# 09_-_PERIPHERALS_B.net
KiCad netlist of a schematic drawn in Altium Designer
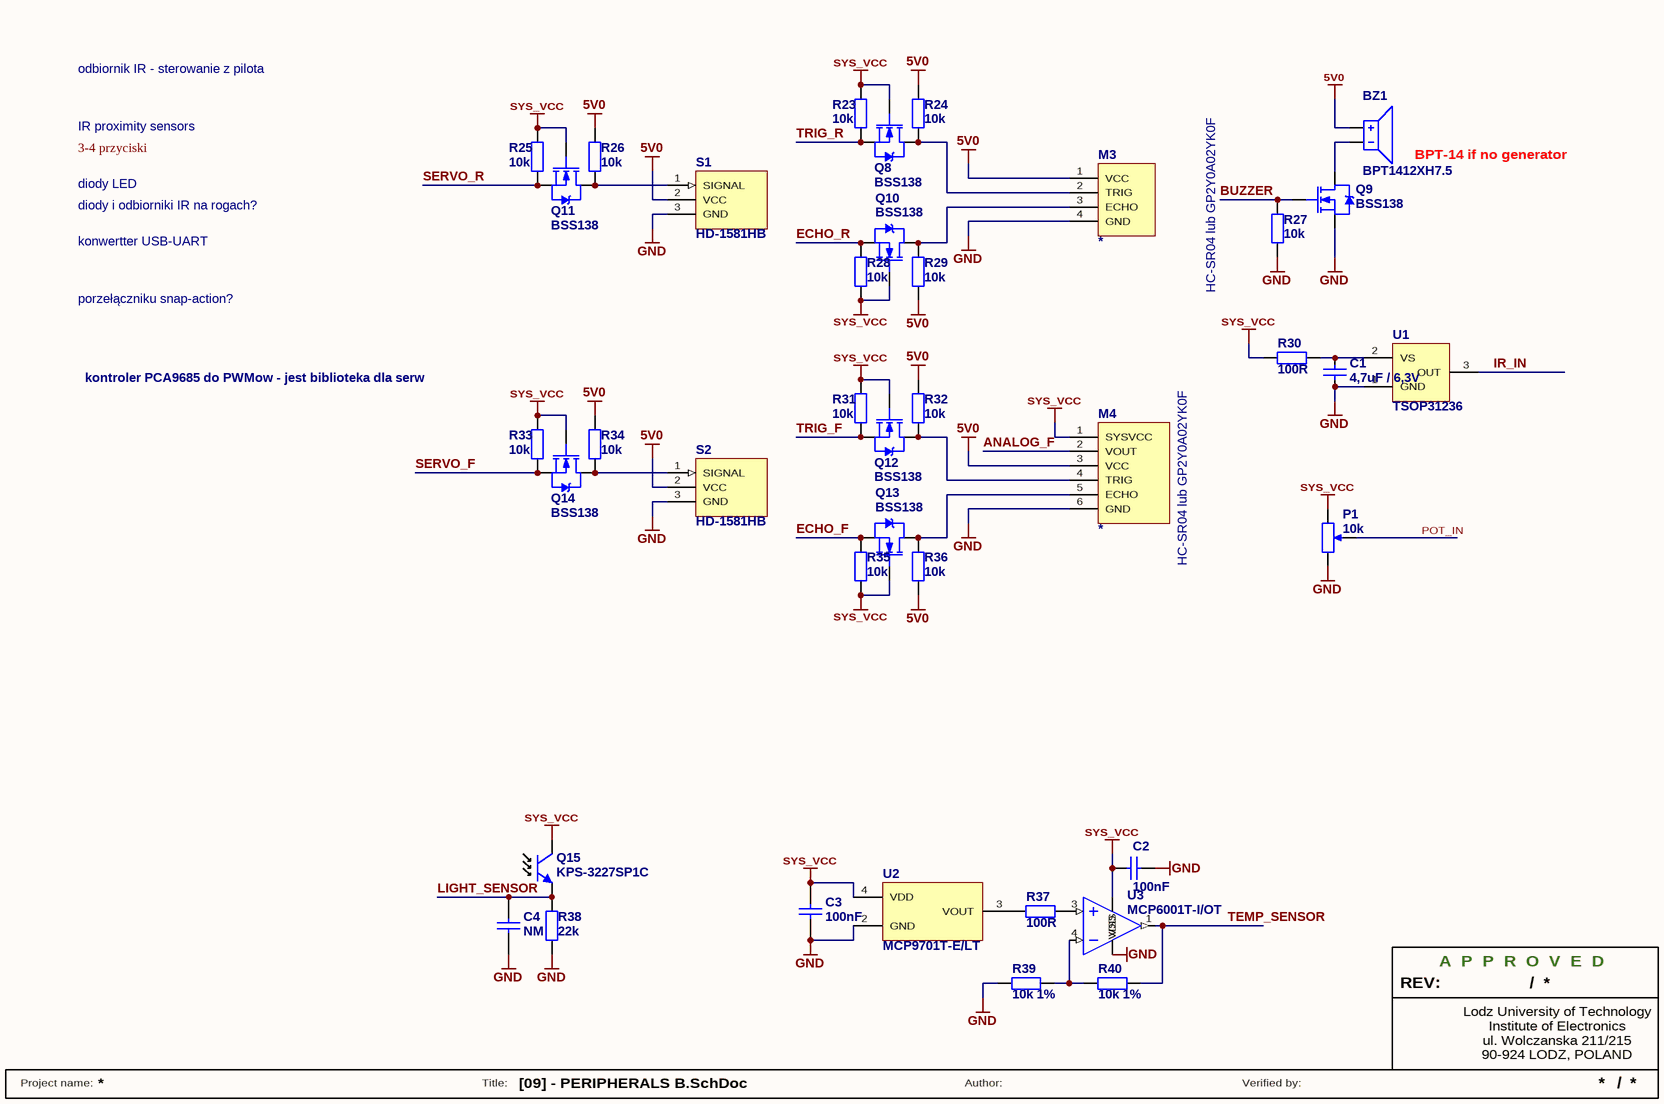
[diagram p0: [09] - PERIPHERALS B.SchDoc]

(export (version "E")
  (design (tool "Eeschema 10.0.6"))
  (components
    (comp (ref "BZ1")
      (value "BPT1412XH7.5")
      (footprint "BUZ-13,8-7,6")
      (description "Piezoelectric Sound Transducer: 5Vp-p; 4kHz; O:14mm; with generator")
      (fields (field (name "PUBLISHER") "Altium Limited"))
      (libsource (lib "sounders") (part "BPT1412XH7.5"))
    )
    (comp (ref "C1")
      (value "4,7uF / 6,3V")
      (footprint "C0805")
      (description "Capacitor")
      (libsource (lib "capacitors") (part "Cap"))
    )
    (comp (ref "C2")
      (value "100nF")
      (footprint "C0805")
      (description "Capacitor")
      (libsource (lib "") (part "Cap_1"))
    )
    (comp (ref "C3")
      (value "100nF")
      (footprint "C0805")
      (description "Capacitor")
      (libsource (lib "") (part "Cap_2"))
    )
    (comp (ref "C4")
      (value "NM")
      (footprint "C0805")
      (description "Capacitor")
      (libsource (lib "") (part "Cap_2"))
    )
    (comp (ref "M3") (value "*") (footprint "HC-SR04") (libsource (lib "other_modules") (part "HC-SR04")))
    (comp (ref "M4")
      (value "*")
      (footprint "HC-SR04_UNIV")
      (libsource (lib "other_modules") (part "HC-SR04_UNIVERSAL"))
    )
    (comp (ref "P1")
      (value "10k")
      (footprint "RK09K113004U")
      (description "RK09K113004U")
      (libsource (lib "resistors") (part "RK09K113004U"))
    )
    (comp (ref "Q8")
      (value "BSS138")
      (footprint "SOT-23")
      (description "N-Channel Enhancement Mode Vertical DMOS FET")
      (fields (field (name "PUBLISHER") "Altium Limited"))
      (libsource (lib "transistors_other") (part "BSS138"))
    )
    (comp (ref "Q9")
      (value "BSS138")
      (footprint "SOT-23")
      (description "N-Channel Enhancement Mode Vertical DMOS FET")
      (fields (field (name "PUBLISHER") "Altium Limited"))
      (libsource (lib "transistors_other") (part "BSS138"))
    )
    (comp (ref "Q10")
      (value "BSS138")
      (footprint "SOT-23")
      (description "N-Channel Enhancement Mode Vertical DMOS FET")
      (fields (field (name "PUBLISHER") "Altium Limited"))
      (libsource (lib "transistors_other") (part "BSS138"))
    )
    (comp (ref "Q11")
      (value "BSS138")
      (footprint "SOT-23")
      (description "N-Channel Enhancement Mode Vertical DMOS FET")
      (fields (field (name "PUBLISHER") "Altium Limited"))
      (libsource (lib "transistors_other") (part "BSS138"))
    )
    (comp (ref "Q12")
      (value "BSS138")
      (footprint "SOT-23")
      (description "N-Channel Enhancement Mode Vertical DMOS FET")
      (fields (field (name "PUBLISHER") "Altium Limited"))
      (libsource (lib "transistors_other") (part "BSS138"))
    )
    (comp (ref "Q13")
      (value "BSS138")
      (footprint "SOT-23")
      (description "N-Channel Enhancement Mode Vertical DMOS FET")
      (fields (field (name "PUBLISHER") "Altium Limited"))
      (libsource (lib "transistors_other") (part "BSS138"))
    )
    (comp (ref "Q14")
      (value "BSS138")
      (footprint "SOT-23")
      (description "N-Channel Enhancement Mode Vertical DMOS FET")
      (fields (field (name "PUBLISHER") "Altium Limited"))
      (libsource (lib "transistors_other") (part "BSS138"))
    )
    (comp (ref "Q15")
      (value "KPS-3227SP1C")
      (footprint "KPS-3227")
      (description "Photo Transistor 60V 0,1mA 580nm (TME KPS-3227SP1C)")
      (libsource (lib "photoelements") (part "KPS-3227SP1C"))
    )
    (comp (ref "R23")
      (value "10k")
      (footprint "R0805")
      (description "Resistor")
      (libsource (lib "resistors") (part "Res"))
    )
    (comp (ref "R24")
      (value "10k")
      (footprint "R0805")
      (description "Resistor")
      (libsource (lib "resistors") (part "Res"))
    )
    (comp (ref "R25")
      (value "10k")
      (footprint "R0805")
      (description "Resistor")
      (libsource (lib "resistors") (part "Res"))
    )
    (comp (ref "R26")
      (value "10k")
      (footprint "R0805")
      (description "Resistor")
      (libsource (lib "resistors") (part "Res"))
    )
    (comp (ref "R27")
      (value "10k")
      (footprint "R0805")
      (description "Resistor")
      (libsource (lib "") (part "Res_3"))
    )
    (comp (ref "R28")
      (value "10k")
      (footprint "R0805")
      (description "Resistor")
      (libsource (lib "") (part "Res_2"))
    )
    (comp (ref "R29")
      (value "10k")
      (footprint "R0805")
      (description "Resistor")
      (libsource (lib "") (part "Res_2"))
    )
    (comp (ref "R30")
      (value "100R")
      (footprint "R0805")
      (description "Resistor")
      (libsource (lib "") (part "Res_4"))
    )
    (comp (ref "R31")
      (value "10k")
      (footprint "R0805")
      (description "Resistor")
      (libsource (lib "resistors") (part "Res"))
    )
    (comp (ref "R32")
      (value "10k")
      (footprint "R0805")
      (description "Resistor")
      (libsource (lib "resistors") (part "Res"))
    )
    (comp (ref "R33")
      (value "10k")
      (footprint "R0805")
      (description "Resistor")
      (libsource (lib "resistors") (part "Res"))
    )
    (comp (ref "R34")
      (value "10k")
      (footprint "R0805")
      (description "Resistor")
      (libsource (lib "resistors") (part "Res"))
    )
    (comp (ref "R35")
      (value "10k")
      (footprint "R0805")
      (description "Resistor")
      (libsource (lib "") (part "Res_2"))
    )
    (comp (ref "R36")
      (value "10k")
      (footprint "R0805")
      (description "Resistor")
      (libsource (lib "") (part "Res_2"))
    )
    (comp (ref "R37")
      (value "100R")
      (footprint "R0805")
      (description "Resistor")
      (libsource (lib "") (part "Res_1"))
    )
    (comp (ref "R38")
      (value "22k")
      (footprint "R0805")
      (description "Resistor")
      (libsource (lib "") (part "Res_3"))
    )
    (comp (ref "R39")
      (value "10k 1%")
      (footprint "R0805")
      (description "Resistor")
      (libsource (lib "") (part "Res_1"))
    )
    (comp (ref "R40")
      (value "10k 1%")
      (footprint "R0805")
      (description "Resistor")
      (libsource (lib "") (part "Res_1"))
    )
    (comp (ref "S1")
      (value "HD-1581HB")
      (footprint "HD-1581HB_VERTICAL_1")
      (description "HD-1581HB Micro Servo")
      (libsource (lib "servos") (part "HD-1581HB"))
    )
    (comp (ref "S2")
      (value "HD-1581HB")
      (footprint "HD-1581HB_VERTICAL_1")
      (description "HD-1581HB Micro Servo")
      (libsource (lib "servos") (part "HD-1581HB"))
    )
    (comp (ref "U1")
      (value "TSOP31236")
      (footprint "TSOP312(4)_H")
      (description "36kHz IR Receiver Module for Remote Control Systems")
      (libsource (lib "ir_receivers") (part "TSOP31236"))
    )
    (comp (ref "U2")
      (value "MCP9701T-E/LT")
      (footprint "SOT-323-5 (SOT-353, SC70-5)")
      (description "Low-Power Linear Active Thermistor IC")
      (libsource (lib "temperature_transducers") (part "MCP9701T-E/LT"))
    )
    (comp (ref "U3")
      (value "MCP6001T-I/OT")
      (footprint "SOT-23-5")
      (description "Rail-to-rail, 1MHz, 100uA Op Amp")
      (libsource (lib "opamps") (part "MCP6001T-I/OT"))
    )
  )
  (nets
    (net (code "2") (name "/ANALOG_F") (class "Default")
      (node (ref "M4") (pin "2") (pinfunction "VOUT_2") (pintype "power_in"))
    )
    (net (code "3") (name "/BUZZER") (class "Default")
      (node (ref "Q9") (pin "1") (pinfunction "G_1") (pintype "passive"))
      (node (ref "R27") (pin "1") (pinfunction "1_1") (pintype "passive"))
    )
    (net (code "4") (name "/ECHO_F") (class "Default")
      (node (ref "Q13") (pin "2") (pinfunction "S_2") (pintype "passive"))
      (node (ref "R35") (pin "1") (pinfunction "1_1") (pintype "passive"))
    )
    (net (code "5") (name "/ECHO_R") (class "Default")
      (node (ref "Q10") (pin "2") (pinfunction "S_2") (pintype "passive"))
      (node (ref "R28") (pin "1") (pinfunction "1_1") (pintype "passive"))
    )
    (net (code "6") (name "/IR_IN") (class "Default")
      (node (ref "U1") (pin "3") (pinfunction "OUT_3") (pintype "passive"))
    )
    (net (code "7") (name "/LIGHT_SENSOR") (class "Default")
      (node (ref "C4") (pin "2") (pinfunction "2_2") (pintype "passive"))
      (node (ref "Q15") (pin "1") (pinfunction "E_1") (pintype "passive"))
      (node (ref "R38") (pin "1") (pinfunction "1_1") (pintype "passive"))
    )
    (net (code "8") (name "/POT_IN") (class "Default")
      (node (ref "P1") (pin "2") (pinfunction "TAP_2") (pintype "passive"))
    )
    (net (code "9") (name "/SERVO_F") (class "Default")
      (node (ref "Q14") (pin "2") (pinfunction "S_2") (pintype "passive"))
      (node (ref "R33") (pin "1") (pinfunction "1_1") (pintype "passive"))
    )
    (net (code "10") (name "/SERVO_R") (class "Default")
      (node (ref "Q11") (pin "2") (pinfunction "S_2") (pintype "passive"))
      (node (ref "R25") (pin "1") (pinfunction "1_1") (pintype "passive"))
    )
    (net (code "11") (name "/TEMP_SENSOR") (class "Default")
      (node (ref "R40") (pin "1") (pinfunction "1_1") (pintype "passive"))
      (node (ref "U3") (pin "1") (pinfunction "OUT_1") (pintype "output"))
    )
    (net (code "12") (name "/TRIG_F") (class "Default")
      (node (ref "Q12") (pin "2") (pinfunction "S_2") (pintype "passive"))
      (node (ref "R31") (pin "1") (pinfunction "1_1") (pintype "passive"))
    )
    (net (code "13") (name "/TRIG_R") (class "Default")
      (node (ref "Q8") (pin "2") (pinfunction "S_2") (pintype "passive"))
      (node (ref "R23") (pin "1") (pinfunction "1_1") (pintype "passive"))
    )
    (net (code "14") (name "5V0") (class "Default")
      (node (ref "BZ1") (pin "1") (pinfunction "1_1") (pintype "passive"))
      (node (ref "M3") (pin "1") (pinfunction "VCC_1") (pintype "power_in"))
      (node (ref "M4") (pin "3") (pinfunction "VCC_3") (pintype "power_in"))
      (node (ref "R24") (pin "2") (pinfunction "2_2") (pintype "passive"))
      (node (ref "R26") (pin "2") (pinfunction "2_2") (pintype "passive"))
      (node (ref "R29") (pin "2") (pinfunction "2_2") (pintype "passive"))
      (node (ref "R32") (pin "2") (pinfunction "2_2") (pintype "passive"))
      (node (ref "R34") (pin "2") (pinfunction "2_2") (pintype "passive"))
      (node (ref "R36") (pin "2") (pinfunction "2_2") (pintype "passive"))
      (node (ref "S1") (pin "2") (pinfunction "VCC_2") (pintype "power_in"))
      (node (ref "S2") (pin "2") (pinfunction "VCC_2") (pintype "power_in"))
    )
    (net (code "15") (name "GND") (class "Default")
      (node (ref "C1") (pin "1") (pinfunction "1_1") (pintype "passive"))
      (node (ref "C2") (pin "2") (pinfunction "2_2") (pintype "passive"))
      (node (ref "C3") (pin "1") (pinfunction "1_1") (pintype "passive"))
      (node (ref "C4") (pin "1") (pinfunction "1_1") (pintype "passive"))
      (node (ref "M3") (pin "4") (pinfunction "GND_4") (pintype "power_in"))
      (node (ref "M4") (pin "6") (pinfunction "GND_6") (pintype "power_in"))
      (node (ref "P1") (pin "3") (pinfunction "BOT_3") (pintype "passive"))
      (node (ref "Q9") (pin "2") (pinfunction "S_2") (pintype "passive"))
      (node (ref "R27") (pin "2") (pinfunction "2_2") (pintype "passive"))
      (node (ref "R38") (pin "2") (pinfunction "2_2") (pintype "passive"))
      (node (ref "R39") (pin "2") (pinfunction "2_2") (pintype "passive"))
      (node (ref "S1") (pin "3") (pinfunction "GND_3") (pintype "power_in"))
      (node (ref "S2") (pin "3") (pinfunction "GND_3") (pintype "power_in"))
      (node (ref "U1") (pin "1") (pinfunction "GND_1") (pintype "passive"))
      (node (ref "U2") (pin "2") (pinfunction "GND_2") (pintype "passive"))
      (node (ref "U3") (pin "2") (pinfunction "VSS_2") (pintype "power_in"))
    )
    (net (code "16") (name "Net-(M3-ECHO)") (class "Default")
      (node (ref "M3") (pin "3") (pinfunction "ECHO_3") (pintype "power_in"))
      (node (ref "Q10") (pin "3") (pinfunction "D_3") (pintype "passive"))
      (node (ref "R29") (pin "1") (pinfunction "1_1") (pintype "passive"))
    )
    (net (code "17") (name "Net-(M3-TRIG)") (class "Default")
      (node (ref "M3") (pin "2") (pinfunction "TRIG_2") (pintype "power_in"))
      (node (ref "Q8") (pin "3") (pinfunction "D_3") (pintype "passive"))
      (node (ref "R24") (pin "1") (pinfunction "1_1") (pintype "passive"))
    )
    (net (code "18") (name "Net-(M4-ECHO)") (class "Default")
      (node (ref "M4") (pin "5") (pinfunction "ECHO_5") (pintype "power_in"))
      (node (ref "Q13") (pin "3") (pinfunction "D_3") (pintype "passive"))
      (node (ref "R36") (pin "1") (pinfunction "1_1") (pintype "passive"))
    )
    (net (code "19") (name "Net-(M4-TRIG)") (class "Default")
      (node (ref "M4") (pin "4") (pinfunction "TRIG_4") (pintype "power_in"))
      (node (ref "Q12") (pin "3") (pinfunction "D_3") (pintype "passive"))
      (node (ref "R32") (pin "1") (pinfunction "1_1") (pintype "passive"))
    )
    (net (code "20") (name "Net-(Q9-D)") (class "Default")
      (node (ref "BZ1") (pin "2") (pinfunction "2_2") (pintype "passive"))
      (node (ref "Q9") (pin "3") (pinfunction "D_3") (pintype "passive"))
    )
    (net (code "21") (name "Net-(Q11-D)") (class "Default")
      (node (ref "Q11") (pin "3") (pinfunction "D_3") (pintype "passive"))
      (node (ref "R26") (pin "1") (pinfunction "1_1") (pintype "passive"))
      (node (ref "S1") (pin "1") (pinfunction "SIGNAL_1") (pintype "input"))
    )
    (net (code "22") (name "Net-(Q14-D)") (class "Default")
      (node (ref "Q14") (pin "3") (pinfunction "D_3") (pintype "passive"))
      (node (ref "R34") (pin "1") (pinfunction "1_1") (pintype "passive"))
      (node (ref "S2") (pin "1") (pinfunction "SIGNAL_1") (pintype "input"))
    )
    (net (code "23") (name "Net-(U1-VS)") (class "Default")
      (node (ref "C1") (pin "2") (pinfunction "2_2") (pintype "passive"))
      (node (ref "R30") (pin "2") (pinfunction "2_2") (pintype "passive"))
      (node (ref "U1") (pin "2") (pinfunction "VS_2") (pintype "passive"))
    )
    (net (code "24") (name "Net-(U2-VOUT)") (class "Default")
      (node (ref "R37") (pin "2") (pinfunction "2_2") (pintype "passive"))
      (node (ref "U2") (pin "3") (pinfunction "VOUT_3") (pintype "passive"))
    )
    (net (code "25") (name "Net-(U3-IN+)") (class "Default")
      (node (ref "R37") (pin "1") (pinfunction "1_1") (pintype "passive"))
      (node (ref "U3") (pin "3") (pinfunction "IN+_3") (pintype "input"))
    )
    (net (code "26") (name "Net-(U3-IN-)") (class "Default")
      (node (ref "R39") (pin "1") (pinfunction "1_1") (pintype "passive"))
      (node (ref "R40") (pin "2") (pinfunction "2_2") (pintype "passive"))
      (node (ref "U3") (pin "4") (pinfunction "IN-_4") (pintype "input"))
    )
    (net (code "27") (name "SYS_VCC") (class "Default")
      (node (ref "C2") (pin "1") (pinfunction "1_1") (pintype "passive"))
      (node (ref "C3") (pin "2") (pinfunction "2_2") (pintype "passive"))
      (node (ref "M4") (pin "1") (pinfunction "SYSVCC_1") (pintype "power_in"))
      (node (ref "P1") (pin "1") (pinfunction "TOP_1") (pintype "passive"))
      (node (ref "Q10") (pin "1") (pinfunction "G_1") (pintype "passive"))
      (node (ref "Q11") (pin "1") (pinfunction "G_1") (pintype "passive"))
      (node (ref "Q12") (pin "1") (pinfunction "G_1") (pintype "passive"))
      (node (ref "Q13") (pin "1") (pinfunction "G_1") (pintype "passive"))
      (node (ref "Q14") (pin "1") (pinfunction "G_1") (pintype "passive"))
      (node (ref "Q15") (pin "2") (pinfunction "C_2") (pintype "passive"))
      (node (ref "Q8") (pin "1") (pinfunction "G_1") (pintype "passive"))
      (node (ref "R23") (pin "2") (pinfunction "2_2") (pintype "passive"))
      (node (ref "R25") (pin "2") (pinfunction "2_2") (pintype "passive"))
      (node (ref "R28") (pin "2") (pinfunction "2_2") (pintype "passive"))
      (node (ref "R30") (pin "1") (pinfunction "1_1") (pintype "passive"))
      (node (ref "R31") (pin "2") (pinfunction "2_2") (pintype "passive"))
      (node (ref "R33") (pin "2") (pinfunction "2_2") (pintype "passive"))
      (node (ref "R35") (pin "2") (pinfunction "2_2") (pintype "passive"))
      (node (ref "U2") (pin "4") (pinfunction "VDD_4") (pintype "passive"))
      (node (ref "U3") (pin "5") (pinfunction "VDD_5") (pintype "power_in"))
    )
  )
)
